# cdcio.net
KiCad netlist of a schematic drawn in EAGLE
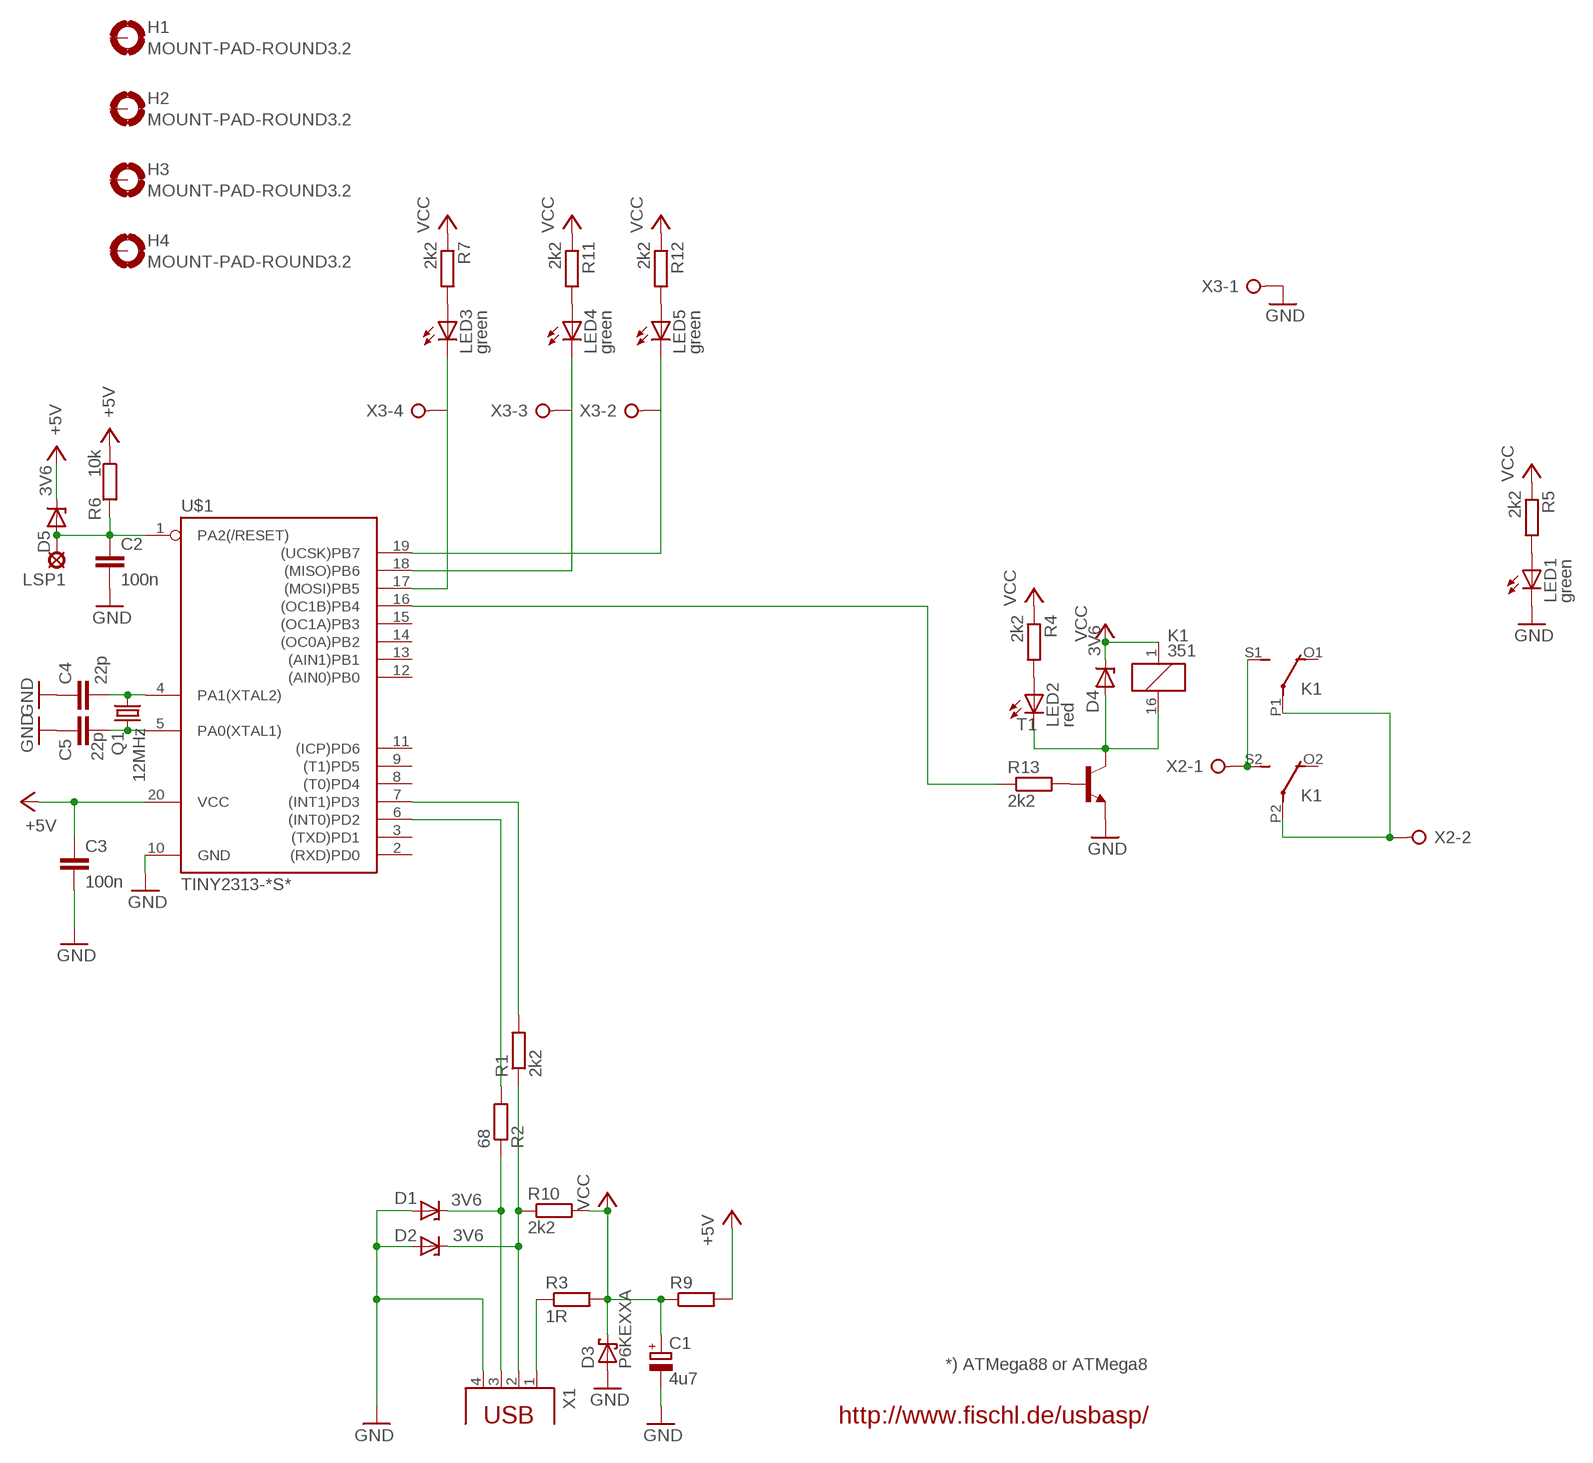
[diagram p0: schematic, sheet 1]

(export (version "E")
  (design (tool "Eeschema 10.0.6"))
  (components
    (comp (ref "C1")
      (value "4u7")
      (footprint "eagle-import:E2,5-5")
      (libsource (lib "eagle-import") (part "CPOL-EUE2.5-5"))
    )
    (comp (ref "C2")
      (value "100n")
      (footprint "eagle-import:C025-024X044")
      (libsource (lib "eagle-import") (part "C-EU025-024X044"))
    )
    (comp (ref "C3")
      (value "100n")
      (footprint "eagle-import:C025-024X044")
      (libsource (lib "eagle-import") (part "C-EU025-024X044"))
    )
    (comp (ref "C4")
      (value "22p")
      (footprint "eagle-import:C025-024X044")
      (libsource (lib "eagle-import") (part "C-EU025-024X044"))
    )
    (comp (ref "C5")
      (value "22p")
      (footprint "eagle-import:C025-024X044")
      (libsource (lib "eagle-import") (part "C-EU025-024X044"))
    )
    (comp (ref "D1")
      (value "3V6")
      (footprint "eagle-import:DO34Z7")
      (libsource (lib "eagle-import") (part "ZENER-DIODEDO34-7"))
    )
    (comp (ref "D2")
      (value "3V6")
      (footprint "eagle-import:DO34Z7")
      (libsource (lib "eagle-import") (part "ZENER-DIODEDO34-7"))
    )
    (comp (ref "D3")
      (value "P6KEXXA")
      (footprint "eagle-import:C1702-15")
      (libsource (lib "eagle-import") (part "P6KEXXA"))
    )
    (comp (ref "D4")
      (value "3V6")
      (footprint "eagle-import:DO34Z7")
      (libsource (lib "eagle-import") (part "ZENER-DIODEDO34-7"))
    )
    (comp (ref "D5")
      (value "3V6")
      (footprint "eagle-import:DO34Z7")
      (libsource (lib "eagle-import") (part "ZENER-DIODEDO34-7"))
    )
    (comp (ref "H1")
      (value "MOUNT-PAD-ROUND3.2")
      (footprint "eagle-import:3,2-PAD")
      (libsource (lib "eagle-import") (part "MOUNT-PAD-ROUND3.2"))
    )
    (comp (ref "H2")
      (value "MOUNT-PAD-ROUND3.2")
      (footprint "eagle-import:3,2-PAD")
      (libsource (lib "eagle-import") (part "MOUNT-PAD-ROUND3.2"))
    )
    (comp (ref "H3")
      (value "MOUNT-PAD-ROUND3.2")
      (footprint "eagle-import:3,2-PAD")
      (libsource (lib "eagle-import") (part "MOUNT-PAD-ROUND3.2"))
    )
    (comp (ref "H4")
      (value "MOUNT-PAD-ROUND3.2")
      (footprint "eagle-import:3,2-PAD")
      (libsource (lib "eagle-import") (part "MOUNT-PAD-ROUND3.2"))
    )
    (comp (ref "K1")
      (value "351")
      (footprint "eagle-import:351")
      (libsource (lib "eagle-import") (part "351"))
    )
    (comp (ref "LED1")
      (value "green")
      (footprint "eagle-import:LED3MM")
      (libsource (lib "eagle-import") (part "LED3MM"))
    )
    (comp (ref "LED2")
      (value "red")
      (footprint "eagle-import:LED3MM")
      (libsource (lib "eagle-import") (part "LED3MM"))
    )
    (comp (ref "LED3")
      (value "green")
      (footprint "eagle-import:LED3MM")
      (libsource (lib "eagle-import") (part "LED3MM"))
    )
    (comp (ref "LED4")
      (value "green")
      (footprint "eagle-import:LED3MM")
      (libsource (lib "eagle-import") (part "LED3MM"))
    )
    (comp (ref "LED5")
      (value "green")
      (footprint "eagle-import:LED3MM")
      (libsource (lib "eagle-import") (part "LED3MM"))
    )
    (comp (ref "LSP1")
      (value "LSP10")
      (footprint "eagle-import:LSP10")
      (libsource (lib "eagle-import") (part "LSP10"))
    )
    (comp (ref "Q1")
      (value "12MHz")
      (footprint "eagle-import:HC49_S")
      (libsource (lib "eagle-import") (part "CRYTALHC49S"))
    )
    (comp (ref "R1")
      (value "2k2")
      (footprint "eagle-import:0207_2V")
      (libsource (lib "eagle-import") (part "R-EU_0207/2V"))
    )
    (comp (ref "R2")
      (value "68")
      (footprint "eagle-import:0207_10")
      (libsource (lib "eagle-import") (part "R-EU_0207/10"))
    )
    (comp (ref "R3")
      (value "1R")
      (footprint "eagle-import:0207_2V")
      (libsource (lib "eagle-import") (part "R-EU_0207/2V"))
    )
    (comp (ref "R4")
      (value "2k2")
      (footprint "eagle-import:0207_2V")
      (libsource (lib "eagle-import") (part "R-EU_0207/2V"))
    )
    (comp (ref "R5")
      (value "2k2")
      (footprint "eagle-import:0207_2V")
      (libsource (lib "eagle-import") (part "R-EU_0207/2V"))
    )
    (comp (ref "R6")
      (value "10k")
      (footprint "eagle-import:0207_10")
      (libsource (lib "eagle-import") (part "R-EU_0207/10"))
    )
    (comp (ref "R7")
      (value "2k2")
      (footprint "eagle-import:0207_2V")
      (libsource (lib "eagle-import") (part "R-EU_0207/2V"))
    )
    (comp (ref "R9")
      (value "R-EU_0207/2V")
      (footprint "eagle-import:0207_2V")
      (libsource (lib "eagle-import") (part "R-EU_0207/2V"))
    )
    (comp (ref "R10")
      (value "2k2")
      (footprint "eagle-import:0207_2V")
      (libsource (lib "eagle-import") (part "R-EU_0207/2V"))
    )
    (comp (ref "R11")
      (value "2k2")
      (footprint "eagle-import:0207_2V")
      (libsource (lib "eagle-import") (part "R-EU_0207/2V"))
    )
    (comp (ref "R12")
      (value "2k2")
      (footprint "eagle-import:0207_2V")
      (libsource (lib "eagle-import") (part "R-EU_0207/2V"))
    )
    (comp (ref "R13")
      (value "2k2")
      (footprint "eagle-import:0207_2V")
      (libsource (lib "eagle-import") (part "R-EU_0207/2V"))
    )
    (comp (ref "T1")
      (value "2N4124-NPN-TO92-CBE")
      (footprint "eagle-import:TO92-CBE")
      (libsource (lib "eagle-import") (part "-NPN-TO92-CBE2N4124"))
    )
    (comp (ref "U$1")
      (value "TINY2313-*S*")
      (footprint "eagle-import:SO20L$")
      (libsource (lib "eagle-import") (part "TINY2313-S"))
    )
    (comp (ref "X1")
      (value "PN61729")
      (footprint "eagle-import:PN61729")
      (libsource (lib "eagle-import") (part "PN61729"))
    )
    (comp (ref "X2")
      (value "W237-02P")
      (footprint "eagle-import:W237-132")
      (libsource (lib "eagle-import") (part "W237-02P"))
    )
    (comp (ref "X3")
      (value "W237-04P")
      (footprint "eagle-import:W237-4P")
      (libsource (lib "eagle-import") (part "W237-04P"))
    )
  )
  (nets
    (net (code "1") (name "+5V") (class "Default")
      (node (ref "C3") (pin "1") (pinfunction "1_1") (pintype "passive"))
      (node (ref "D5") (pin "C") (pinfunction "C_C") (pintype "passive"))
      (node (ref "R6") (pin "1") (pinfunction "1_1") (pintype "passive"))
      (node (ref "R9") (pin "2") (pinfunction "2_2") (pintype "passive"))
      (node (ref "U$1") (pin "20") (pinfunction "VCC_20") (pintype "power_in"))
    )
    (net (code "2") (name "GND") (class "Default")
      (node (ref "C1") (pin "-") (pinfunction "-_-") (pintype "passive"))
      (node (ref "C2") (pin "2") (pinfunction "2_2") (pintype "passive"))
      (node (ref "C3") (pin "2") (pinfunction "2_2") (pintype "passive"))
      (node (ref "C4") (pin "1") (pinfunction "1_1") (pintype "passive"))
      (node (ref "C5") (pin "1") (pinfunction "1_1") (pintype "passive"))
      (node (ref "D1") (pin "A") (pinfunction "A_A") (pintype "passive"))
      (node (ref "D2") (pin "A") (pinfunction "A_A") (pintype "passive"))
      (node (ref "D3") (pin "A") (pinfunction "A_A") (pintype "passive"))
      (node (ref "LED1") (pin "K") (pinfunction "C_K") (pintype "passive"))
      (node (ref "T1") (pin "E") (pinfunction "E_E") (pintype "passive"))
      (node (ref "U$1") (pin "10") (pinfunction "GND_10") (pintype "power_in"))
      (node (ref "X1") (pin "4") (pinfunction "4_4") (pintype "bidirectional"))
      (node (ref "X3") (pin "1") (pinfunction "KL_1") (pintype "passive"))
    )
    (net (code "3") (name "Net-(D1-PadC)") (class "Default")
      (node (ref "D1") (pin "C") (pinfunction "C_C") (pintype "passive"))
      (node (ref "R2") (pin "1") (pinfunction "1_1") (pintype "passive"))
      (node (ref "X1") (pin "3") (pinfunction "3_3") (pintype "bidirectional"))
    )
    (net (code "4") (name "Net-(D2-PadC)") (class "Default")
      (node (ref "D2") (pin "C") (pinfunction "C_C") (pintype "passive"))
      (node (ref "R1") (pin "1") (pinfunction "1_1") (pintype "passive"))
      (node (ref "R10") (pin "1") (pinfunction "1_1") (pintype "passive"))
      (node (ref "X1") (pin "2") (pinfunction "2_2") (pintype "bidirectional"))
    )
    (net (code "5") (name "Net-(K1A-2)") (class "Default")
      (node (ref "D4") (pin "A") (pinfunction "A_A") (pintype "passive"))
      (node (ref "K1") (pin "16") (pinfunction "2_16") (pintype "passive"))
      (node (ref "LED2") (pin "K") (pinfunction "C_K") (pintype "passive"))
      (node (ref "T1") (pin "C") (pinfunction "C_C") (pintype "passive"))
    )
    (net (code "6") (name "Net-(K1B-P)") (class "Default")
      (node (ref "K1") (pin "P1") (pinfunction "P_P1") (pintype "passive"))
      (node (ref "K1") (pin "P2") (pinfunction "P_P2") (pintype "passive"))
      (node (ref "X2") (pin "2") (pinfunction "KL_2") (pintype "passive"))
    )
    (net (code "7") (name "Net-(K1B-S)") (class "Default")
      (node (ref "K1") (pin "S1") (pinfunction "S_S1") (pintype "passive"))
      (node (ref "K1") (pin "S2") (pinfunction "S_S2") (pintype "passive"))
      (node (ref "X2") (pin "1") (pinfunction "KL_1") (pintype "passive"))
    )
    (net (code "8") (name "Net-(LED1-PadA)") (class "Default")
      (node (ref "LED1") (pin "A") (pinfunction "A_A") (pintype "passive"))
      (node (ref "R5") (pin "2") (pinfunction "2_2") (pintype "passive"))
    )
    (net (code "9") (name "Net-(LED2-PadA)") (class "Default")
      (node (ref "LED2") (pin "A") (pinfunction "A_A") (pintype "passive"))
      (node (ref "R4") (pin "2") (pinfunction "2_2") (pintype "passive"))
    )
    (net (code "10") (name "Net-(LED3-C)") (class "Default")
      (node (ref "LED3") (pin "K") (pinfunction "C_K") (pintype "passive"))
      (node (ref "U$1") (pin "17") (pinfunction "(MOSI)PB5_17") (pintype "bidirectional"))
      (node (ref "X3") (pin "4") (pinfunction "KL_4") (pintype "passive"))
    )
    (net (code "11") (name "Net-(LED3-PadA)") (class "Default")
      (node (ref "LED3") (pin "A") (pinfunction "A_A") (pintype "passive"))
      (node (ref "R7") (pin "2") (pinfunction "2_2") (pintype "passive"))
    )
    (net (code "12") (name "Net-(LED4-C)") (class "Default")
      (node (ref "LED4") (pin "K") (pinfunction "C_K") (pintype "passive"))
      (node (ref "U$1") (pin "18") (pinfunction "(MISO)PB6_18") (pintype "bidirectional"))
      (node (ref "X3") (pin "3") (pinfunction "KL_3") (pintype "passive"))
    )
    (net (code "13") (name "Net-(LED4-PadA)") (class "Default")
      (node (ref "LED4") (pin "A") (pinfunction "A_A") (pintype "passive"))
      (node (ref "R11") (pin "2") (pinfunction "2_2") (pintype "passive"))
    )
    (net (code "14") (name "Net-(LED5-C)") (class "Default")
      (node (ref "LED5") (pin "K") (pinfunction "C_K") (pintype "passive"))
      (node (ref "U$1") (pin "19") (pinfunction "(UCSK)PB7_19") (pintype "bidirectional"))
      (node (ref "X3") (pin "2") (pinfunction "KL_2") (pintype "passive"))
    )
    (net (code "15") (name "Net-(LED5-PadA)") (class "Default")
      (node (ref "LED5") (pin "A") (pinfunction "A_A") (pintype "passive"))
      (node (ref "R12") (pin "2") (pinfunction "2_2") (pintype "passive"))
    )
    (net (code "16") (name "Net-(R3-Pad1)") (class "Default")
      (node (ref "R3") (pin "1") (pinfunction "1_1") (pintype "passive"))
      (node (ref "X1") (pin "1") (pinfunction "1_1") (pintype "bidirectional"))
    )
    (net (code "17") (name "Net-(R13-Pad2)") (class "Default")
      (node (ref "R13") (pin "2") (pinfunction "2_2") (pintype "passive"))
      (node (ref "T1") (pin "B") (pinfunction "B_B") (pintype "passive"))
    )
    (net (code "18") (name "Net-(U$1-(INT0)PD2)") (class "Default")
      (node (ref "R2") (pin "2") (pinfunction "2_2") (pintype "passive"))
      (node (ref "U$1") (pin "6") (pinfunction "(INT0)PD2_6") (pintype "bidirectional"))
    )
    (net (code "19") (name "Net-(U$1-(INT1)PD3)") (class "Default")
      (node (ref "R1") (pin "2") (pinfunction "2_2") (pintype "passive"))
      (node (ref "U$1") (pin "7") (pinfunction "(INT1)PD3_7") (pintype "bidirectional"))
    )
    (net (code "20") (name "Net-(U$1-(OC1B)PB4)") (class "Default")
      (node (ref "R13") (pin "1") (pinfunction "1_1") (pintype "passive"))
      (node (ref "U$1") (pin "16") (pinfunction "(OC1B)PB4_16") (pintype "bidirectional"))
    )
    (net (code "21") (name "Net-(U$1-PA0(XTAL1))") (class "Default")
      (node (ref "C5") (pin "2") (pinfunction "2_2") (pintype "passive"))
      (node (ref "Q1") (pin "1") (pinfunction "1_1") (pintype "passive"))
      (node (ref "U$1") (pin "5") (pinfunction "PA0(XTAL1)_5") (pintype "bidirectional"))
    )
    (net (code "22") (name "Net-(U$1-PA1(XTAL2))") (class "Default")
      (node (ref "C4") (pin "2") (pinfunction "2_2") (pintype "passive"))
      (node (ref "Q1") (pin "2") (pinfunction "2_2") (pintype "passive"))
      (node (ref "U$1") (pin "4") (pinfunction "PA1(XTAL2)_4") (pintype "bidirectional"))
    )
    (net (code "23") (name "Net-(U$1-PA2({slash}RESET))") (class "Default")
      (node (ref "C2") (pin "1") (pinfunction "1_1") (pintype "passive"))
      (node (ref "D5") (pin "A") (pinfunction "A_A") (pintype "passive"))
      (node (ref "LSP1") (pin "MP") (pinfunction "MP_MP") (pintype "passive"))
      (node (ref "R6") (pin "2") (pinfunction "2_2") (pintype "passive"))
      (node (ref "U$1") (pin "1") (pinfunction "PA2(/RESET)_1") (pintype "input"))
    )
    (net (code "24") (name "VCC") (class "Default")
      (node (ref "C1") (pin "+") (pinfunction "+_+") (pintype "passive"))
      (node (ref "D3") (pin "C") (pinfunction "C_C") (pintype "passive"))
      (node (ref "D4") (pin "C") (pinfunction "C_C") (pintype "passive"))
      (node (ref "K1") (pin "1") (pinfunction "1_1") (pintype "passive"))
      (node (ref "R10") (pin "2") (pinfunction "2_2") (pintype "passive"))
      (node (ref "R11") (pin "1") (pinfunction "1_1") (pintype "passive"))
      (node (ref "R12") (pin "1") (pinfunction "1_1") (pintype "passive"))
      (node (ref "R3") (pin "2") (pinfunction "2_2") (pintype "passive"))
      (node (ref "R4") (pin "1") (pinfunction "1_1") (pintype "passive"))
      (node (ref "R5") (pin "1") (pinfunction "1_1") (pintype "passive"))
      (node (ref "R7") (pin "1") (pinfunction "1_1") (pintype "passive"))
      (node (ref "R9") (pin "1") (pinfunction "1_1") (pintype "passive"))
    )
    (net (code "25") (name "unconnected-(H1-MOUNT-PadB3,2)") (class "Default")
      (node (ref "H1") (pin "B3,2") (pinfunction "MOUNT_B3,2") (pintype "passive"))
    )
    (net (code "26") (name "unconnected-(H2-MOUNT-PadB3,2)") (class "Default")
      (node (ref "H2") (pin "B3,2") (pinfunction "MOUNT_B3,2") (pintype "passive"))
    )
    (net (code "27") (name "unconnected-(H3-MOUNT-PadB3,2)") (class "Default")
      (node (ref "H3") (pin "B3,2") (pinfunction "MOUNT_B3,2") (pintype "passive"))
    )
    (net (code "28") (name "unconnected-(H4-MOUNT-PadB3,2)") (class "Default")
      (node (ref "H4") (pin "B3,2") (pinfunction "MOUNT_B3,2") (pintype "passive"))
    )
    (net (code "29") (name "unconnected-(K1B-O-PadO1)") (class "Default")
      (node (ref "K1") (pin "O1") (pinfunction "O_O1") (pintype "passive"))
    )
    (net (code "30") (name "unconnected-(K1C-O-PadO2)") (class "Default")
      (node (ref "K1") (pin "O2") (pinfunction "O_O2") (pintype "passive"))
    )
    (net (code "31") (name "unconnected-(U$1-(AIN0)PB0-Pad12)") (class "Default")
      (node (ref "U$1") (pin "12") (pinfunction "(AIN0)PB0_12") (pintype "bidirectional"))
    )
    (net (code "32") (name "unconnected-(U$1-(AIN1)PB1-Pad13)") (class "Default")
      (node (ref "U$1") (pin "13") (pinfunction "(AIN1)PB1_13") (pintype "bidirectional"))
    )
    (net (code "33") (name "unconnected-(U$1-(ICP)PD6-Pad11)") (class "Default")
      (node (ref "U$1") (pin "11") (pinfunction "(ICP)PD6_11") (pintype "bidirectional"))
    )
    (net (code "34") (name "unconnected-(U$1-(OC0A)PB2-Pad14)") (class "Default")
      (node (ref "U$1") (pin "14") (pinfunction "(OC0A)PB2_14") (pintype "bidirectional"))
    )
    (net (code "35") (name "unconnected-(U$1-(OC1A)PB3-Pad15)") (class "Default")
      (node (ref "U$1") (pin "15") (pinfunction "(OC1A)PB3_15") (pintype "bidirectional"))
    )
    (net (code "36") (name "unconnected-(U$1-(RXD)PD0-Pad2)") (class "Default")
      (node (ref "U$1") (pin "2") (pinfunction "(RXD)PD0_2") (pintype "bidirectional"))
    )
    (net (code "37") (name "unconnected-(U$1-(T0)PD4-Pad8)") (class "Default")
      (node (ref "U$1") (pin "8") (pinfunction "(T0)PD4_8") (pintype "bidirectional"))
    )
    (net (code "38") (name "unconnected-(U$1-(T1)PD5-Pad9)") (class "Default")
      (node (ref "U$1") (pin "9") (pinfunction "(T1)PD5_9") (pintype "bidirectional"))
    )
    (net (code "39") (name "unconnected-(U$1-(TXD)PD1-Pad3)") (class "Default")
      (node (ref "U$1") (pin "3") (pinfunction "(TXD)PD1_3") (pintype "bidirectional"))
    )
  )
)
